# DigitalPart.net
KiCad netlist of a schematic drawn in Altium Designer
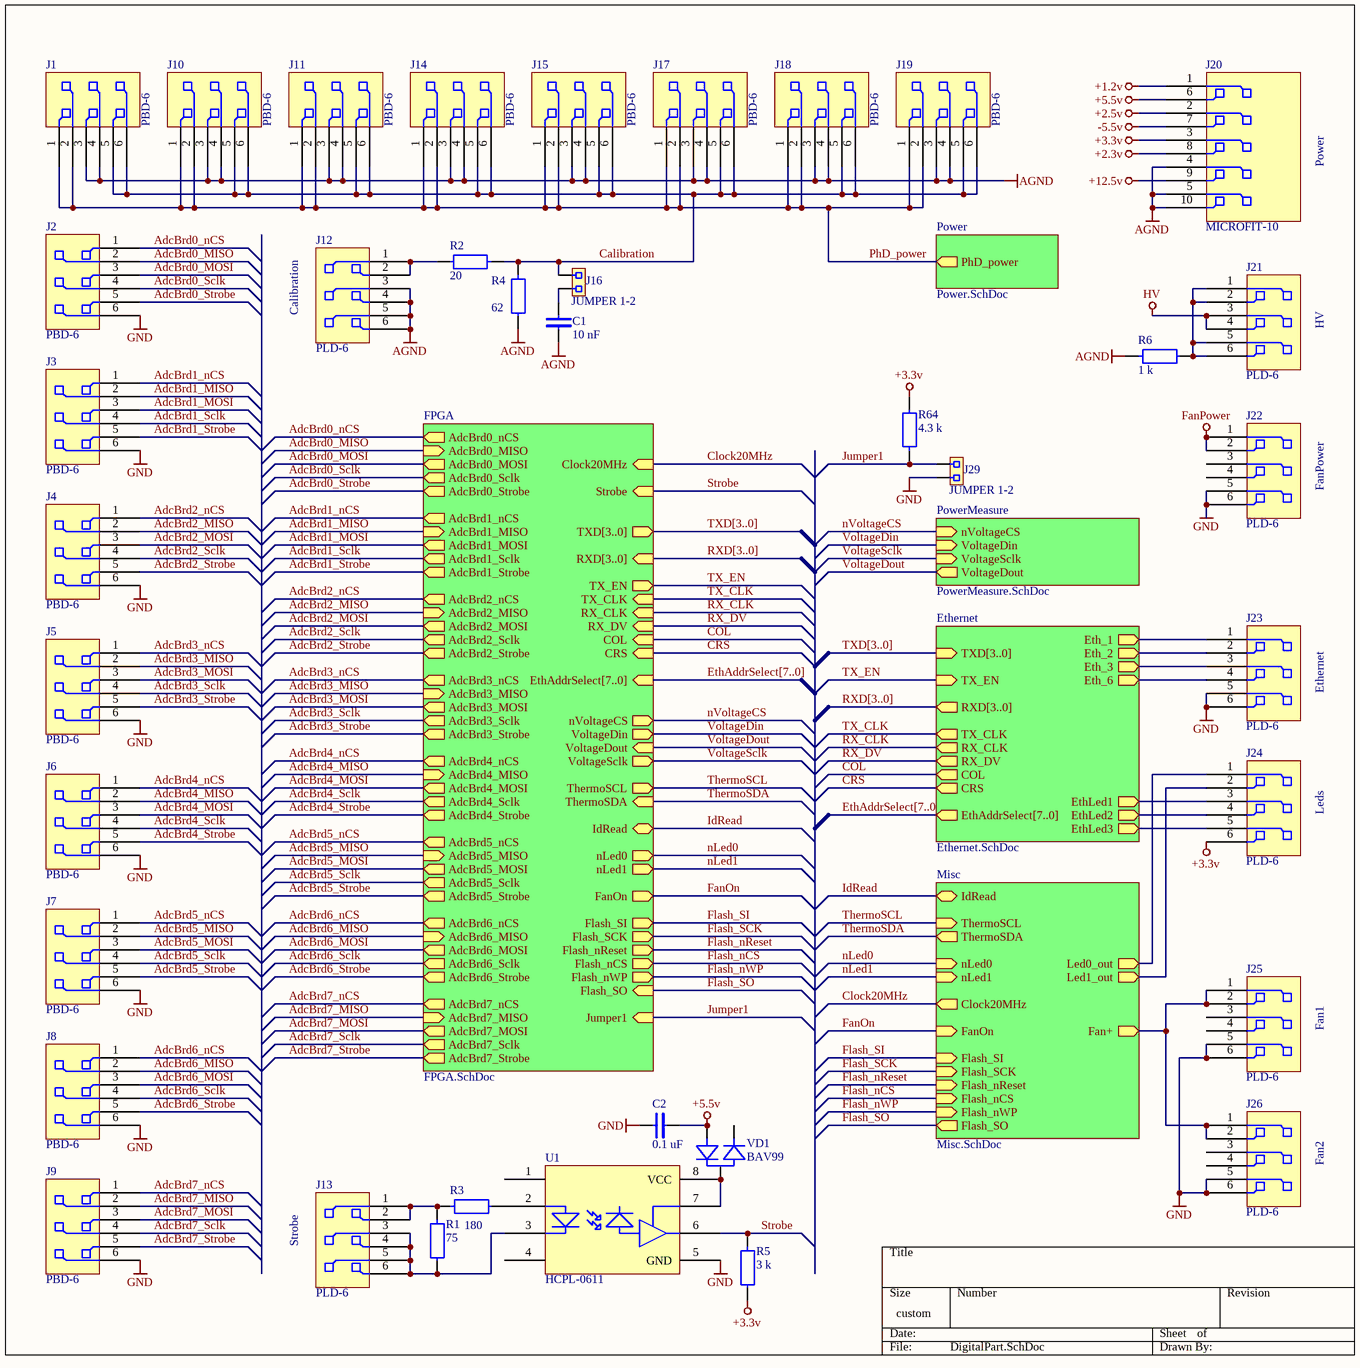
[diagram p0: DigitalPart.SchDoc]

(export (version "E")
  (design (tool "Eeschema 10.0.6"))
  (components
    (comp (ref "C1") (value "10 nF") (footprint "1206") (libsource (lib "*") (part "C")))
    (comp (ref "C2") (value "0.1 uF") (footprint "1206") (libsource (lib "*") (part "C")))
    (comp (ref "J1")
      (value "PBD-6")
      (footprint "PBD-6")
      (description "Socket, double line, 2.54 mm and 2 mm,")
      (libsource (lib "AConnectors") (part "PBD-6"))
    )
    (comp (ref "J2")
      (value "PBD-6")
      (footprint "PBD-6")
      (description "Socket, double line, 2.54 mm and 2 mm,")
      (libsource (lib "") (part "PBD-6_1"))
    )
    (comp (ref "J3")
      (value "PBD-6")
      (footprint "PBD-6")
      (description "Socket, double line, 2.54 mm and 2 mm,")
      (libsource (lib "") (part "PBD-6_1"))
    )
    (comp (ref "J4")
      (value "PBD-6")
      (footprint "PBD-6")
      (description "Socket, double line, 2.54 mm and 2 mm,")
      (libsource (lib "") (part "PBD-6_1"))
    )
    (comp (ref "J5")
      (value "PBD-6")
      (footprint "PBD-6")
      (description "Socket, double line, 2.54 mm and 2 mm,")
      (libsource (lib "") (part "PBD-6_1"))
    )
    (comp (ref "J6")
      (value "PBD-6")
      (footprint "PBD-6")
      (description "Socket, double line, 2.54 mm and 2 mm,")
      (libsource (lib "") (part "PBD-6_1"))
    )
    (comp (ref "J7")
      (value "PBD-6")
      (footprint "PBD-6")
      (description "Socket, double line, 2.54 mm and 2 mm,")
      (libsource (lib "") (part "PBD-6_1"))
    )
    (comp (ref "J8")
      (value "PBD-6")
      (footprint "PBD-6")
      (description "Socket, double line, 2.54 mm and 2 mm,")
      (libsource (lib "") (part "PBD-6_1"))
    )
    (comp (ref "J9")
      (value "PBD-6")
      (footprint "PBD-6")
      (description "Socket, double line, 2.54 mm and 2 mm,")
      (libsource (lib "") (part "PBD-6_1"))
    )
    (comp (ref "J10")
      (value "PBD-6")
      (footprint "PBD-6")
      (description "Socket, double line, 2.54 mm and 2 mm,")
      (libsource (lib "AConnectors") (part "PBD-6"))
    )
    (comp (ref "J11")
      (value "PBD-6")
      (footprint "PBD-6")
      (description "Socket, double line, 2.54 mm and 2 mm,")
      (libsource (lib "AConnectors") (part "PBD-6"))
    )
    (comp (ref "J12") (value "PLD-6") (footprint "PLD-6") (libsource (lib "") (part "PLD-6_1")))
    (comp (ref "J13") (value "PLD-6") (footprint "PLD-6") (libsource (lib "") (part "PLD-6_1")))
    (comp (ref "J14")
      (value "PBD-6")
      (footprint "PBD-6")
      (description "Socket, double line, 2.54 mm and 2 mm,")
      (libsource (lib "AConnectors") (part "PBD-6"))
    )
    (comp (ref "J15")
      (value "PBD-6")
      (footprint "PBD-6")
      (description "Socket, double line, 2.54 mm and 2 mm,")
      (libsource (lib "AConnectors") (part "PBD-6"))
    )
    (comp (ref "J16")
      (value "JUMPER 1-2")
      (footprint "2SIP")
      (description "2.54 mm jumper")
      (libsource (lib "AConnectors") (part "JUMPER 1-2"))
    )
    (comp (ref "J17")
      (value "PBD-6")
      (footprint "PBD-6")
      (description "Socket, double line, 2.54 mm and 2 mm,")
      (libsource (lib "AConnectors") (part "PBD-6"))
    )
    (comp (ref "J18")
      (value "PBD-6")
      (footprint "PBD-6")
      (description "Socket, double line, 2.54 mm and 2 mm,")
      (libsource (lib "AConnectors") (part "PBD-6"))
    )
    (comp (ref "J19")
      (value "PBD-6")
      (footprint "PBD-6")
      (description "Socket, double line, 2.54 mm and 2 mm,")
      (libsource (lib "AConnectors") (part "PBD-6"))
    )
    (comp (ref "J20")
      (value "MICROFIT-10")
      (footprint "MicroFit10")
      (libsource (lib "AConnectors") (part "MICROFIT-10"))
    )
    (comp (ref "J21") (value "PLD-6") (footprint "PLD-6") (libsource (lib "AConnectors") (part "PLD-6")))
    (comp (ref "J22") (value "PLD-6") (footprint "PLD-6") (libsource (lib "AConnectors") (part "PLD-6")))
    (comp (ref "J23") (value "PLD-6") (footprint "PLD-6") (libsource (lib "AConnectors") (part "PLD-6")))
    (comp (ref "J24") (value "PLD-6") (footprint "PLD-6") (libsource (lib "AConnectors") (part "PLD-6")))
    (comp (ref "J25") (value "PLD-6") (footprint "PLD-6") (libsource (lib "AConnectors") (part "PLD-6")))
    (comp (ref "J26") (value "PLD-6") (footprint "PLD-6") (libsource (lib "AConnectors") (part "PLD-6")))
    (comp (ref "J29")
      (value "JUMPER 1-2")
      (footprint "2SIP")
      (description "2.54 mm jumper")
      (libsource (lib "AConnectors") (part "JUMPER 1-2"))
    )
    (comp (ref "R1") (value "75") (footprint "1206") (libsource (lib "*") (part "R")))
    (comp (ref "R2") (value "20") (footprint "1206") (libsource (lib "Adevice") (part "r")))
    (comp (ref "R3") (value "180") (footprint "1206") (libsource (lib "*") (part "R")))
    (comp (ref "R4") (value "62") (footprint "1206") (libsource (lib "Adevice") (part "r")))
    (comp (ref "R5") (value "3 k") (footprint "1206") (libsource (lib "*") (part "R")))
    (comp (ref "R6") (value "1 k") (footprint "1206") (libsource (lib "Adevice") (part "r")))
    (comp (ref "R64") (value "4.3 k") (footprint "0603") (libsource (lib "*") (part "R")))
    (comp (ref "U1") (value "HCPL-0611") (footprint "8SOIC150") (libsource (lib "Mylib") (part "HCPL-0611")))
    (comp (ref "VD1")
      (value "BAV99")
      (footprint "SOT-23")
      (description "Double diode")
      (libsource (lib "Vdiode") (part "BAV99"))
    )
  )
  (nets
    (net (code "17") (name "+1.2v") (class "Default")
      (node (ref "J20") (pin "1") (pinfunction "1_1") (pintype "passive"))
    )
    (net (code "18") (name "+2.3v") (class "Default")
      (node (ref "J20") (pin "8") (pinfunction "8_8") (pintype "passive"))
    )
    (net (code "19") (name "+2.5v") (class "Default")
      (node (ref "J20") (pin "2") (pinfunction "2_2") (pintype "passive"))
    )
    (net (code "20") (name "+3.3v") (class "Default")
      (node (ref "J20") (pin "3") (pinfunction "3_3") (pintype "passive"))
      (node (ref "J24") (pin "6") (pinfunction "6_6") (pintype "passive"))
      (node (ref "R5") (pin "1") (pinfunction "1_1") (pintype "passive"))
      (node (ref "R64") (pin "1") (pinfunction "1_1") (pintype "passive"))
    )
    (net (code "21") (name "+5.5v") (class "Default")
      (node (ref "C2") (pin "2") (pinfunction "2_2") (pintype "passive"))
      (node (ref "J20") (pin "6") (pinfunction "6_6") (pintype "passive"))
      (node (ref "VD1") (pin "1") (pinfunction "1_1") (pintype "passive"))
    )
    (net (code "22") (name "+12.5v") (class "Default")
      (node (ref "J20") (pin "9") (pinfunction "9_9") (pintype "passive"))
    )
    (net (code "23") (name "-5.5v") (class "Default")
      (node (ref "J20") (pin "7") (pinfunction "7_7") (pintype "passive"))
    )
    (net (code "24") (name "/AdcBrd0_MISO") (class "Default")
      (node (ref "J2") (pin "2") (pinfunction "2_2") (pintype "passive"))
    )
    (net (code "25") (name "/AdcBrd0_MOSI") (class "Default")
      (node (ref "J2") (pin "3") (pinfunction "3_3") (pintype "passive"))
    )
    (net (code "26") (name "/AdcBrd0_Sclk") (class "Default")
      (node (ref "J2") (pin "4") (pinfunction "4_4") (pintype "passive"))
    )
    (net (code "27") (name "/AdcBrd0_Strobe") (class "Default")
      (node (ref "J2") (pin "5") (pinfunction "5_5") (pintype "passive"))
    )
    (net (code "28") (name "/AdcBrd0_nCS") (class "Default")
      (node (ref "J2") (pin "1") (pinfunction "1_1") (pintype "passive"))
    )
    (net (code "29") (name "/AdcBrd1_MISO") (class "Default")
      (node (ref "J3") (pin "2") (pinfunction "2_2") (pintype "passive"))
    )
    (net (code "30") (name "/AdcBrd1_MOSI") (class "Default")
      (node (ref "J3") (pin "3") (pinfunction "3_3") (pintype "passive"))
    )
    (net (code "31") (name "/AdcBrd1_Sclk") (class "Default")
      (node (ref "J3") (pin "4") (pinfunction "4_4") (pintype "passive"))
    )
    (net (code "32") (name "/AdcBrd1_Strobe") (class "Default")
      (node (ref "J3") (pin "5") (pinfunction "5_5") (pintype "passive"))
    )
    (net (code "33") (name "/AdcBrd1_nCS") (class "Default")
      (node (ref "J3") (pin "1") (pinfunction "1_1") (pintype "passive"))
    )
    (net (code "34") (name "/AdcBrd2_MISO") (class "Default")
      (node (ref "J4") (pin "2") (pinfunction "2_2") (pintype "passive"))
    )
    (net (code "35") (name "/AdcBrd2_MOSI") (class "Default")
      (node (ref "J4") (pin "3") (pinfunction "3_3") (pintype "passive"))
    )
    (net (code "36") (name "/AdcBrd2_Sclk") (class "Default")
      (node (ref "J4") (pin "4") (pinfunction "4_4") (pintype "passive"))
    )
    (net (code "37") (name "/AdcBrd2_Strobe") (class "Default")
      (node (ref "J4") (pin "5") (pinfunction "5_5") (pintype "passive"))
    )
    (net (code "38") (name "/AdcBrd2_nCS") (class "Default")
      (node (ref "J4") (pin "1") (pinfunction "1_1") (pintype "passive"))
    )
    (net (code "39") (name "/AdcBrd3_MISO") (class "Default")
      (node (ref "J5") (pin "2") (pinfunction "2_2") (pintype "passive"))
    )
    (net (code "40") (name "/AdcBrd3_MOSI") (class "Default")
      (node (ref "J5") (pin "3") (pinfunction "3_3") (pintype "passive"))
    )
    (net (code "41") (name "/AdcBrd3_Sclk") (class "Default")
      (node (ref "J5") (pin "4") (pinfunction "4_4") (pintype "passive"))
    )
    (net (code "42") (name "/AdcBrd3_Strobe") (class "Default")
      (node (ref "J5") (pin "5") (pinfunction "5_5") (pintype "passive"))
    )
    (net (code "43") (name "/AdcBrd3_nCS") (class "Default")
      (node (ref "J5") (pin "1") (pinfunction "1_1") (pintype "passive"))
    )
    (net (code "44") (name "/AdcBrd4_MISO") (class "Default")
      (node (ref "J6") (pin "2") (pinfunction "2_2") (pintype "passive"))
    )
    (net (code "45") (name "/AdcBrd4_MOSI") (class "Default")
      (node (ref "J6") (pin "3") (pinfunction "3_3") (pintype "passive"))
    )
    (net (code "46") (name "/AdcBrd4_Sclk") (class "Default")
      (node (ref "J6") (pin "4") (pinfunction "4_4") (pintype "passive"))
    )
    (net (code "47") (name "/AdcBrd4_Strobe") (class "Default")
      (node (ref "J6") (pin "5") (pinfunction "5_5") (pintype "passive"))
    )
    (net (code "48") (name "/AdcBrd4_nCS") (class "Default")
      (node (ref "J6") (pin "1") (pinfunction "1_1") (pintype "passive"))
    )
    (net (code "49") (name "/AdcBrd5_MISO") (class "Default")
      (node (ref "J7") (pin "2") (pinfunction "2_2") (pintype "passive"))
    )
    (net (code "50") (name "/AdcBrd5_MOSI") (class "Default")
      (node (ref "J7") (pin "3") (pinfunction "3_3") (pintype "passive"))
    )
    (net (code "51") (name "/AdcBrd5_Sclk") (class "Default")
      (node (ref "J7") (pin "4") (pinfunction "4_4") (pintype "passive"))
    )
    (net (code "52") (name "/AdcBrd5_Strobe") (class "Default")
      (node (ref "J7") (pin "5") (pinfunction "5_5") (pintype "passive"))
    )
    (net (code "53") (name "/AdcBrd5_nCS") (class "Default")
      (node (ref "J7") (pin "1") (pinfunction "1_1") (pintype "passive"))
    )
    (net (code "54") (name "/AdcBrd6_MISO") (class "Default")
      (node (ref "J8") (pin "2") (pinfunction "2_2") (pintype "passive"))
    )
    (net (code "55") (name "/AdcBrd6_MOSI") (class "Default")
      (node (ref "J8") (pin "3") (pinfunction "3_3") (pintype "passive"))
    )
    (net (code "56") (name "/AdcBrd6_Sclk") (class "Default")
      (node (ref "J8") (pin "4") (pinfunction "4_4") (pintype "passive"))
    )
    (net (code "57") (name "/AdcBrd6_Strobe") (class "Default")
      (node (ref "J8") (pin "5") (pinfunction "5_5") (pintype "passive"))
    )
    (net (code "58") (name "/AdcBrd6_nCS") (class "Default")
      (node (ref "J8") (pin "1") (pinfunction "1_1") (pintype "passive"))
    )
    (net (code "59") (name "/AdcBrd7_MISO") (class "Default")
      (node (ref "J9") (pin "2") (pinfunction "2_2") (pintype "passive"))
    )
    (net (code "60") (name "/AdcBrd7_MOSI") (class "Default")
      (node (ref "J9") (pin "3") (pinfunction "3_3") (pintype "passive"))
    )
    (net (code "61") (name "/AdcBrd7_Sclk") (class "Default")
      (node (ref "J9") (pin "4") (pinfunction "4_4") (pintype "passive"))
    )
    (net (code "62") (name "/AdcBrd7_Strobe") (class "Default")
      (node (ref "J9") (pin "5") (pinfunction "5_5") (pintype "passive"))
    )
    (net (code "63") (name "/AdcBrd7_nCS") (class "Default")
      (node (ref "J9") (pin "1") (pinfunction "1_1") (pintype "passive"))
    )
    (net (code "66") (name "/Calibration") (class "Default")
      (node (ref "J1") (pin "5") (pinfunction "5_5") (pintype "passive"))
      (node (ref "J1") (pin "6") (pinfunction "6_6") (pintype "passive"))
      (node (ref "J10") (pin "5") (pinfunction "5_5") (pintype "passive"))
      (node (ref "J10") (pin "6") (pinfunction "6_6") (pintype "passive"))
      (node (ref "J11") (pin "5") (pinfunction "5_5") (pintype "passive"))
      (node (ref "J11") (pin "6") (pinfunction "6_6") (pintype "passive"))
      (node (ref "J14") (pin "5") (pinfunction "5_5") (pintype "passive"))
      (node (ref "J14") (pin "6") (pinfunction "6_6") (pintype "passive"))
      (node (ref "J15") (pin "5") (pinfunction "5_5") (pintype "passive"))
      (node (ref "J15") (pin "6") (pinfunction "6_6") (pintype "passive"))
      (node (ref "J16") (pin "1") (pinfunction "1_1") (pintype "passive"))
      (node (ref "J17") (pin "5") (pinfunction "5_5") (pintype "passive"))
      (node (ref "J17") (pin "6") (pinfunction "6_6") (pintype "passive"))
      (node (ref "J18") (pin "5") (pinfunction "5_5") (pintype "passive"))
      (node (ref "J18") (pin "6") (pinfunction "6_6") (pintype "passive"))
      (node (ref "J19") (pin "5") (pinfunction "5_5") (pintype "passive"))
      (node (ref "J19") (pin "6") (pinfunction "6_6") (pintype "passive"))
      (node (ref "R2") (pin "2") (pinfunction "2_2") (pintype "passive"))
      (node (ref "R4") (pin "2") (pinfunction "2_2") (pintype "passive"))
    )
    (net (code "69") (name "/EthLed1") (class "Default")
      (node (ref "J24") (pin "3") (pinfunction "3_3") (pintype "passive"))
    )
    (net (code "70") (name "/EthLed2") (class "Default")
      (node (ref "J24") (pin "4") (pinfunction "4_4") (pintype "passive"))
    )
    (net (code "71") (name "/EthLed3") (class "Default")
      (node (ref "J24") (pin "5") (pinfunction "5_5") (pintype "passive"))
    )
    (net (code "72") (name "/Eth_1") (class "Default")
      (node (ref "J23") (pin "1") (pinfunction "1_1") (pintype "passive"))
    )
    (net (code "73") (name "/Eth_2") (class "Default")
      (node (ref "J23") (pin "2") (pinfunction "2_2") (pintype "passive"))
    )
    (net (code "74") (name "/Eth_3") (class "Default")
      (node (ref "J23") (pin "3") (pinfunction "3_3") (pintype "passive"))
    )
    (net (code "75") (name "/Eth_6") (class "Default")
      (node (ref "J23") (pin "4") (pinfunction "4_4") (pintype "passive"))
    )
    (net (code "76") (name "/Fan+") (class "Default")
      (node (ref "J25") (pin "1") (pinfunction "1_1") (pintype "passive"))
      (node (ref "J25") (pin "2") (pinfunction "2_2") (pintype "passive"))
      (node (ref "J26") (pin "1") (pinfunction "1_1") (pintype "passive"))
      (node (ref "J26") (pin "2") (pinfunction "2_2") (pintype "passive"))
    )
    (net (code "85") (name "/Jumper1") (class "Default")
      (node (ref "J29") (pin "1") (pinfunction "1_1") (pintype "passive"))
      (node (ref "R64") (pin "2") (pinfunction "2_2") (pintype "passive"))
    )
    (net (code "86") (name "/Led0_out") (class "Default")
      (node (ref "J24") (pin "1") (pinfunction "1_1") (pintype "passive"))
    )
    (net (code "87") (name "/Led1_out") (class "Default")
      (node (ref "J24") (pin "2") (pinfunction "2_2") (pintype "passive"))
    )
    (net (code "88") (name "/PhD_power") (class "Default")
      (node (ref "J1") (pin "1") (pinfunction "1_1") (pintype "passive"))
      (node (ref "J1") (pin "2") (pinfunction "2_2") (pintype "passive"))
      (node (ref "J10") (pin "1") (pinfunction "1_1") (pintype "passive"))
      (node (ref "J10") (pin "2") (pinfunction "2_2") (pintype "passive"))
      (node (ref "J11") (pin "1") (pinfunction "1_1") (pintype "passive"))
      (node (ref "J11") (pin "2") (pinfunction "2_2") (pintype "passive"))
      (node (ref "J14") (pin "1") (pinfunction "1_1") (pintype "passive"))
      (node (ref "J14") (pin "2") (pinfunction "2_2") (pintype "passive"))
      (node (ref "J15") (pin "1") (pinfunction "1_1") (pintype "passive"))
      (node (ref "J15") (pin "2") (pinfunction "2_2") (pintype "passive"))
      (node (ref "J17") (pin "1") (pinfunction "1_1") (pintype "passive"))
      (node (ref "J17") (pin "2") (pinfunction "2_2") (pintype "passive"))
      (node (ref "J18") (pin "1") (pinfunction "1_1") (pintype "passive"))
      (node (ref "J18") (pin "2") (pinfunction "2_2") (pintype "passive"))
      (node (ref "J19") (pin "1") (pinfunction "1_1") (pintype "passive"))
      (node (ref "J19") (pin "2") (pinfunction "2_2") (pintype "passive"))
    )
    (net (code "92") (name "/Strobe") (class "Default")
      (node (ref "R5") (pin "2") (pinfunction "2_2") (pintype "passive"))
      (node (ref "U1") (pin "6") (pinfunction "Out_6") (pintype "passive"))
    )
    (net (code "104") (name "AGND") (class "Default")
      (node (ref "C1") (pin "1") (pinfunction "1_1") (pintype "passive"))
      (node (ref "J1") (pin "3") (pinfunction "3_3") (pintype "passive"))
      (node (ref "J1") (pin "4") (pinfunction "4_4") (pintype "passive"))
      (node (ref "J10") (pin "3") (pinfunction "3_3") (pintype "passive"))
      (node (ref "J10") (pin "4") (pinfunction "4_4") (pintype "passive"))
      (node (ref "J11") (pin "3") (pinfunction "3_3") (pintype "passive"))
      (node (ref "J11") (pin "4") (pinfunction "4_4") (pintype "passive"))
      (node (ref "J12") (pin "3") (pinfunction "3_3") (pintype "passive"))
      (node (ref "J12") (pin "4") (pinfunction "4_4") (pintype "passive"))
      (node (ref "J12") (pin "5") (pinfunction "5_5") (pintype "passive"))
      (node (ref "J12") (pin "6") (pinfunction "6_6") (pintype "passive"))
      (node (ref "J14") (pin "3") (pinfunction "3_3") (pintype "passive"))
      (node (ref "J14") (pin "4") (pinfunction "4_4") (pintype "passive"))
      (node (ref "J15") (pin "3") (pinfunction "3_3") (pintype "passive"))
      (node (ref "J15") (pin "4") (pinfunction "4_4") (pintype "passive"))
      (node (ref "J17") (pin "3") (pinfunction "3_3") (pintype "passive"))
      (node (ref "J17") (pin "4") (pinfunction "4_4") (pintype "passive"))
      (node (ref "J18") (pin "3") (pinfunction "3_3") (pintype "passive"))
      (node (ref "J18") (pin "4") (pinfunction "4_4") (pintype "passive"))
      (node (ref "J19") (pin "3") (pinfunction "3_3") (pintype "passive"))
      (node (ref "J19") (pin "4") (pinfunction "4_4") (pintype "passive"))
      (node (ref "J20") (pin "10") (pinfunction "10_10") (pintype "passive"))
      (node (ref "J20") (pin "4") (pinfunction "4_4") (pintype "passive"))
      (node (ref "J20") (pin "5") (pinfunction "5_5") (pintype "passive"))
      (node (ref "R4") (pin "1") (pinfunction "1_1") (pintype "passive"))
      (node (ref "R6") (pin "2") (pinfunction "2_2") (pintype "passive"))
    )
    (net (code "105") (name "FanPower") (class "Default")
      (node (ref "J22") (pin "1") (pinfunction "1_1") (pintype "passive"))
      (node (ref "J22") (pin "2") (pinfunction "2_2") (pintype "passive"))
    )
    (net (code "106") (name "GND") (class "Default")
      (node (ref "C2") (pin "1") (pinfunction "1_1") (pintype "passive"))
      (node (ref "J2") (pin "6") (pinfunction "6_6") (pintype "passive"))
      (node (ref "J22") (pin "5") (pinfunction "5_5") (pintype "passive"))
      (node (ref "J22") (pin "6") (pinfunction "6_6") (pintype "passive"))
      (node (ref "J23") (pin "5") (pinfunction "5_5") (pintype "passive"))
      (node (ref "J23") (pin "6") (pinfunction "6_6") (pintype "passive"))
      (node (ref "J25") (pin "5") (pinfunction "5_5") (pintype "passive"))
      (node (ref "J25") (pin "6") (pinfunction "6_6") (pintype "passive"))
      (node (ref "J26") (pin "5") (pinfunction "5_5") (pintype "passive"))
      (node (ref "J26") (pin "6") (pinfunction "6_6") (pintype "passive"))
      (node (ref "J29") (pin "2") (pinfunction "2_2") (pintype "passive"))
      (node (ref "J3") (pin "6") (pinfunction "6_6") (pintype "passive"))
      (node (ref "J4") (pin "6") (pinfunction "6_6") (pintype "passive"))
      (node (ref "J5") (pin "6") (pinfunction "6_6") (pintype "passive"))
      (node (ref "J6") (pin "6") (pinfunction "6_6") (pintype "passive"))
      (node (ref "J7") (pin "6") (pinfunction "6_6") (pintype "passive"))
      (node (ref "J8") (pin "6") (pinfunction "6_6") (pintype "passive"))
      (node (ref "J9") (pin "6") (pinfunction "6_6") (pintype "passive"))
      (node (ref "U1") (pin "5") (pinfunction "GND_5") (pintype "passive"))
    )
    (net (code "107") (name "HV") (class "Default")
      (node (ref "J21") (pin "3") (pinfunction "3_3") (pintype "passive"))
      (node (ref "J21") (pin "4") (pinfunction "4_4") (pintype "passive"))
    )
    (net (code "108") (name "Net-(C1-Pad2)") (class "Default")
      (node (ref "C1") (pin "2") (pinfunction "2_2") (pintype "passive"))
      (node (ref "J16") (pin "2") (pinfunction "2_2") (pintype "passive"))
    )
    (net (code "109") (name "Net-(J12-Pad1)") (class "Default")
      (node (ref "J12") (pin "1") (pinfunction "1_1") (pintype "passive"))
      (node (ref "J12") (pin "2") (pinfunction "2_2") (pintype "passive"))
      (node (ref "R2") (pin "1") (pinfunction "1_1") (pintype "passive"))
    )
    (net (code "110") (name "Net-(J13-Pad1)") (class "Default")
      (node (ref "J13") (pin "1") (pinfunction "1_1") (pintype "passive"))
      (node (ref "J13") (pin "2") (pinfunction "2_2") (pintype "passive"))
      (node (ref "R1") (pin "2") (pinfunction "2_2") (pintype "passive"))
      (node (ref "R3") (pin "2") (pinfunction "2_2") (pintype "passive"))
    )
    (net (code "111") (name "Net-(J21-Pad1)") (class "Default")
      (node (ref "J21") (pin "1") (pinfunction "1_1") (pintype "passive"))
      (node (ref "J21") (pin "2") (pinfunction "2_2") (pintype "passive"))
      (node (ref "J21") (pin "5") (pinfunction "5_5") (pintype "passive"))
      (node (ref "J21") (pin "6") (pinfunction "6_6") (pintype "passive"))
      (node (ref "R6") (pin "1") (pinfunction "1_1") (pintype "passive"))
    )
    (net (code "112") (name "Net-(U1-In+)") (class "Default")
      (node (ref "R3") (pin "1") (pinfunction "1_1") (pintype "passive"))
      (node (ref "U1") (pin "2") (pinfunction "In+_2") (pintype "passive"))
    )
    (net (code "113") (name "Net-(U1-In-)") (class "Default")
      (node (ref "J13") (pin "3") (pinfunction "3_3") (pintype "passive"))
      (node (ref "J13") (pin "4") (pinfunction "4_4") (pintype "passive"))
      (node (ref "J13") (pin "5") (pinfunction "5_5") (pintype "passive"))
      (node (ref "J13") (pin "6") (pinfunction "6_6") (pintype "passive"))
      (node (ref "R1") (pin "1") (pinfunction "1_1") (pintype "passive"))
      (node (ref "U1") (pin "3") (pinfunction "In-_3") (pintype "passive"))
    )
    (net (code "114") (name "Net-(U1-VCC)") (class "Default")
      (node (ref "U1") (pin "7") (pinfunction "Ve_7") (pintype "passive"))
      (node (ref "U1") (pin "8") (pinfunction "VCC_8") (pintype "passive"))
      (node (ref "VD1") (pin "3") (pinfunction "3_3") (pintype "passive"))
    )
    (net (code "115") (name "unconnected-(J22-Pad3)") (class "Default")
      (node (ref "J22") (pin "3") (pinfunction "3_3") (pintype "passive"))
    )
    (net (code "116") (name "unconnected-(J22-Pad4)") (class "Default")
      (node (ref "J22") (pin "4") (pinfunction "4_4") (pintype "passive"))
    )
    (net (code "117") (name "unconnected-(J25-Pad3)") (class "Default")
      (node (ref "J25") (pin "3") (pinfunction "3_3") (pintype "passive"))
    )
    (net (code "118") (name "unconnected-(J25-Pad4)") (class "Default")
      (node (ref "J25") (pin "4") (pinfunction "4_4") (pintype "passive"))
    )
    (net (code "119") (name "unconnected-(J26-Pad3)") (class "Default")
      (node (ref "J26") (pin "3") (pinfunction "3_3") (pintype "passive"))
    )
    (net (code "120") (name "unconnected-(J26-Pad4)") (class "Default")
      (node (ref "J26") (pin "4") (pinfunction "4_4") (pintype "passive"))
    )
    (net (code "121") (name "unconnected-(U1-NC-Pad1)") (class "Default")
      (node (ref "U1") (pin "1") (pinfunction "NC_1") (pintype "passive"))
    )
    (net (code "122") (name "unconnected-(U1-NC-Pad4)") (class "Default")
      (node (ref "U1") (pin "4") (pinfunction "NC_4") (pintype "passive"))
    )
    (net (code "123") (name "unconnected-(VD1-Pad2)") (class "Default")
      (node (ref "VD1") (pin "2") (pinfunction "2_2") (pintype "passive"))
    )
  )
)
